# RFM69_NRF_adapter.net
KiCad netlist of a schematic drawn in EAGLE
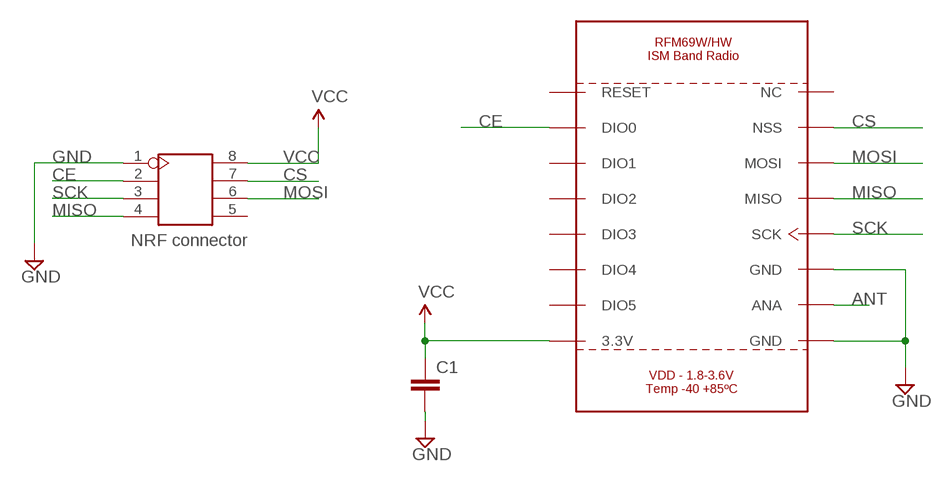
[diagram p0: schematic, sheet 1]

(export (version "E")
  (design (tool "Eeschema 10.0.6"))
  (components
    (comp (ref "C1")
      (value "C-EUC1206K")
      (footprint "eagle-import:C1206K")
      (libsource (lib "eagle-import") (part "C-EUC1206K"))
    )
    (comp (ref "J1")
      (value "NRF connector")
      (footprint "eagle-import:2X4P-2.54")
      (libsource (lib "eagle-import") (part "HEADER-2X4P-2.54"))
    )
    (comp (ref "U$1")
      (value "RFM69W/HW-")
      (footprint "eagle-import:RFM69W_HW")
      (libsource (lib "eagle-import") (part "RFM69W/HW-"))
    )
  )
  (nets
    (net (code "1") (name "/ANT") (class "Default")
      (node (ref "U$1") (pin "P$10") (pinfunction "ANA_P$10") (pintype "bidirectional"))
    )
    (net (code "2") (name "/CE") (class "Default")
      (node (ref "J1") (pin "2") (pinfunction "2_2") (pintype "bidirectional"))
      (node (ref "U$1") (pin "P$2") (pinfunction "DIO0_P$2") (pintype "bidirectional"))
    )
    (net (code "3") (name "/CS") (class "Default")
      (node (ref "J1") (pin "7") (pinfunction "7_7") (pintype "bidirectional"))
      (node (ref "U$1") (pin "P$15") (pinfunction "NSS_P$15") (pintype "bidirectional"))
    )
    (net (code "4") (name "/MISO") (class "Default")
      (node (ref "J1") (pin "4") (pinfunction "4_4") (pintype "bidirectional"))
      (node (ref "U$1") (pin "P$13") (pinfunction "MISO_P$13") (pintype "bidirectional"))
    )
    (net (code "5") (name "/MOSI") (class "Default")
      (node (ref "J1") (pin "6") (pinfunction "6_6") (pintype "bidirectional"))
      (node (ref "U$1") (pin "P$14") (pinfunction "MOSI_P$14") (pintype "bidirectional"))
    )
    (net (code "6") (name "/SCK") (class "Default")
      (node (ref "J1") (pin "3") (pinfunction "3_3") (pintype "bidirectional"))
      (node (ref "U$1") (pin "P$12") (pinfunction "SCK_P$12") (pintype "bidirectional"))
    )
    (net (code "7") (name "GND") (class "Default")
      (node (ref "C1") (pin "2") (pinfunction "2_2") (pintype "passive"))
      (node (ref "J1") (pin "1") (pinfunction "1_1") (pintype "bidirectional"))
      (node (ref "U$1") (pin "P$11") (pinfunction "GND_P$11") (pintype "power_in"))
      (node (ref "U$1") (pin "P$9") (pinfunction "GND_P$9") (pintype "power_in"))
    )
    (net (code "8") (name "VCC") (class "Default")
      (node (ref "C1") (pin "1") (pinfunction "1_1") (pintype "passive"))
      (node (ref "J1") (pin "8") (pinfunction "8_8") (pintype "bidirectional"))
      (node (ref "U$1") (pin "P$8") (pinfunction "3.3V_P$8") (pintype "power_in"))
    )
    (net (code "9") (name "unconnected-(J1-Pad5)") (class "Default")
      (node (ref "J1") (pin "5") (pinfunction "5_5") (pintype "bidirectional"))
    )
    (net (code "10") (name "unconnected-(U$1-DIO1-PadP$3)") (class "Default")
      (node (ref "U$1") (pin "P$3") (pinfunction "DIO1_P$3") (pintype "bidirectional"))
    )
    (net (code "11") (name "unconnected-(U$1-DIO2-PadP$4)") (class "Default")
      (node (ref "U$1") (pin "P$4") (pinfunction "DIO2_P$4") (pintype "bidirectional"))
    )
    (net (code "12") (name "unconnected-(U$1-DIO3-PadP$5)") (class "Default")
      (node (ref "U$1") (pin "P$5") (pinfunction "DIO3_P$5") (pintype "bidirectional"))
    )
    (net (code "13") (name "unconnected-(U$1-DIO4-PadP$6)") (class "Default")
      (node (ref "U$1") (pin "P$6") (pinfunction "DIO4_P$6") (pintype "bidirectional"))
    )
    (net (code "14") (name "unconnected-(U$1-DIO5-PadP$7)") (class "Default")
      (node (ref "U$1") (pin "P$7") (pinfunction "DIO5_P$7") (pintype "bidirectional"))
    )
    (net (code "15") (name "unconnected-(U$1-NC-PadP$16)") (class "Default")
      (node (ref "U$1") (pin "P$16") (pinfunction "NC_P$16") (pintype "no_connect"))
    )
    (net (code "16") (name "unconnected-(U$1-RESET-PadP$1)") (class "Default")
      (node (ref "U$1") (pin "P$1") (pinfunction "RESET_P$1") (pintype "bidirectional"))
    )
  )
)
